# record_revc_ad8228.net
KiCad netlist of a schematic drawn in EAGLE
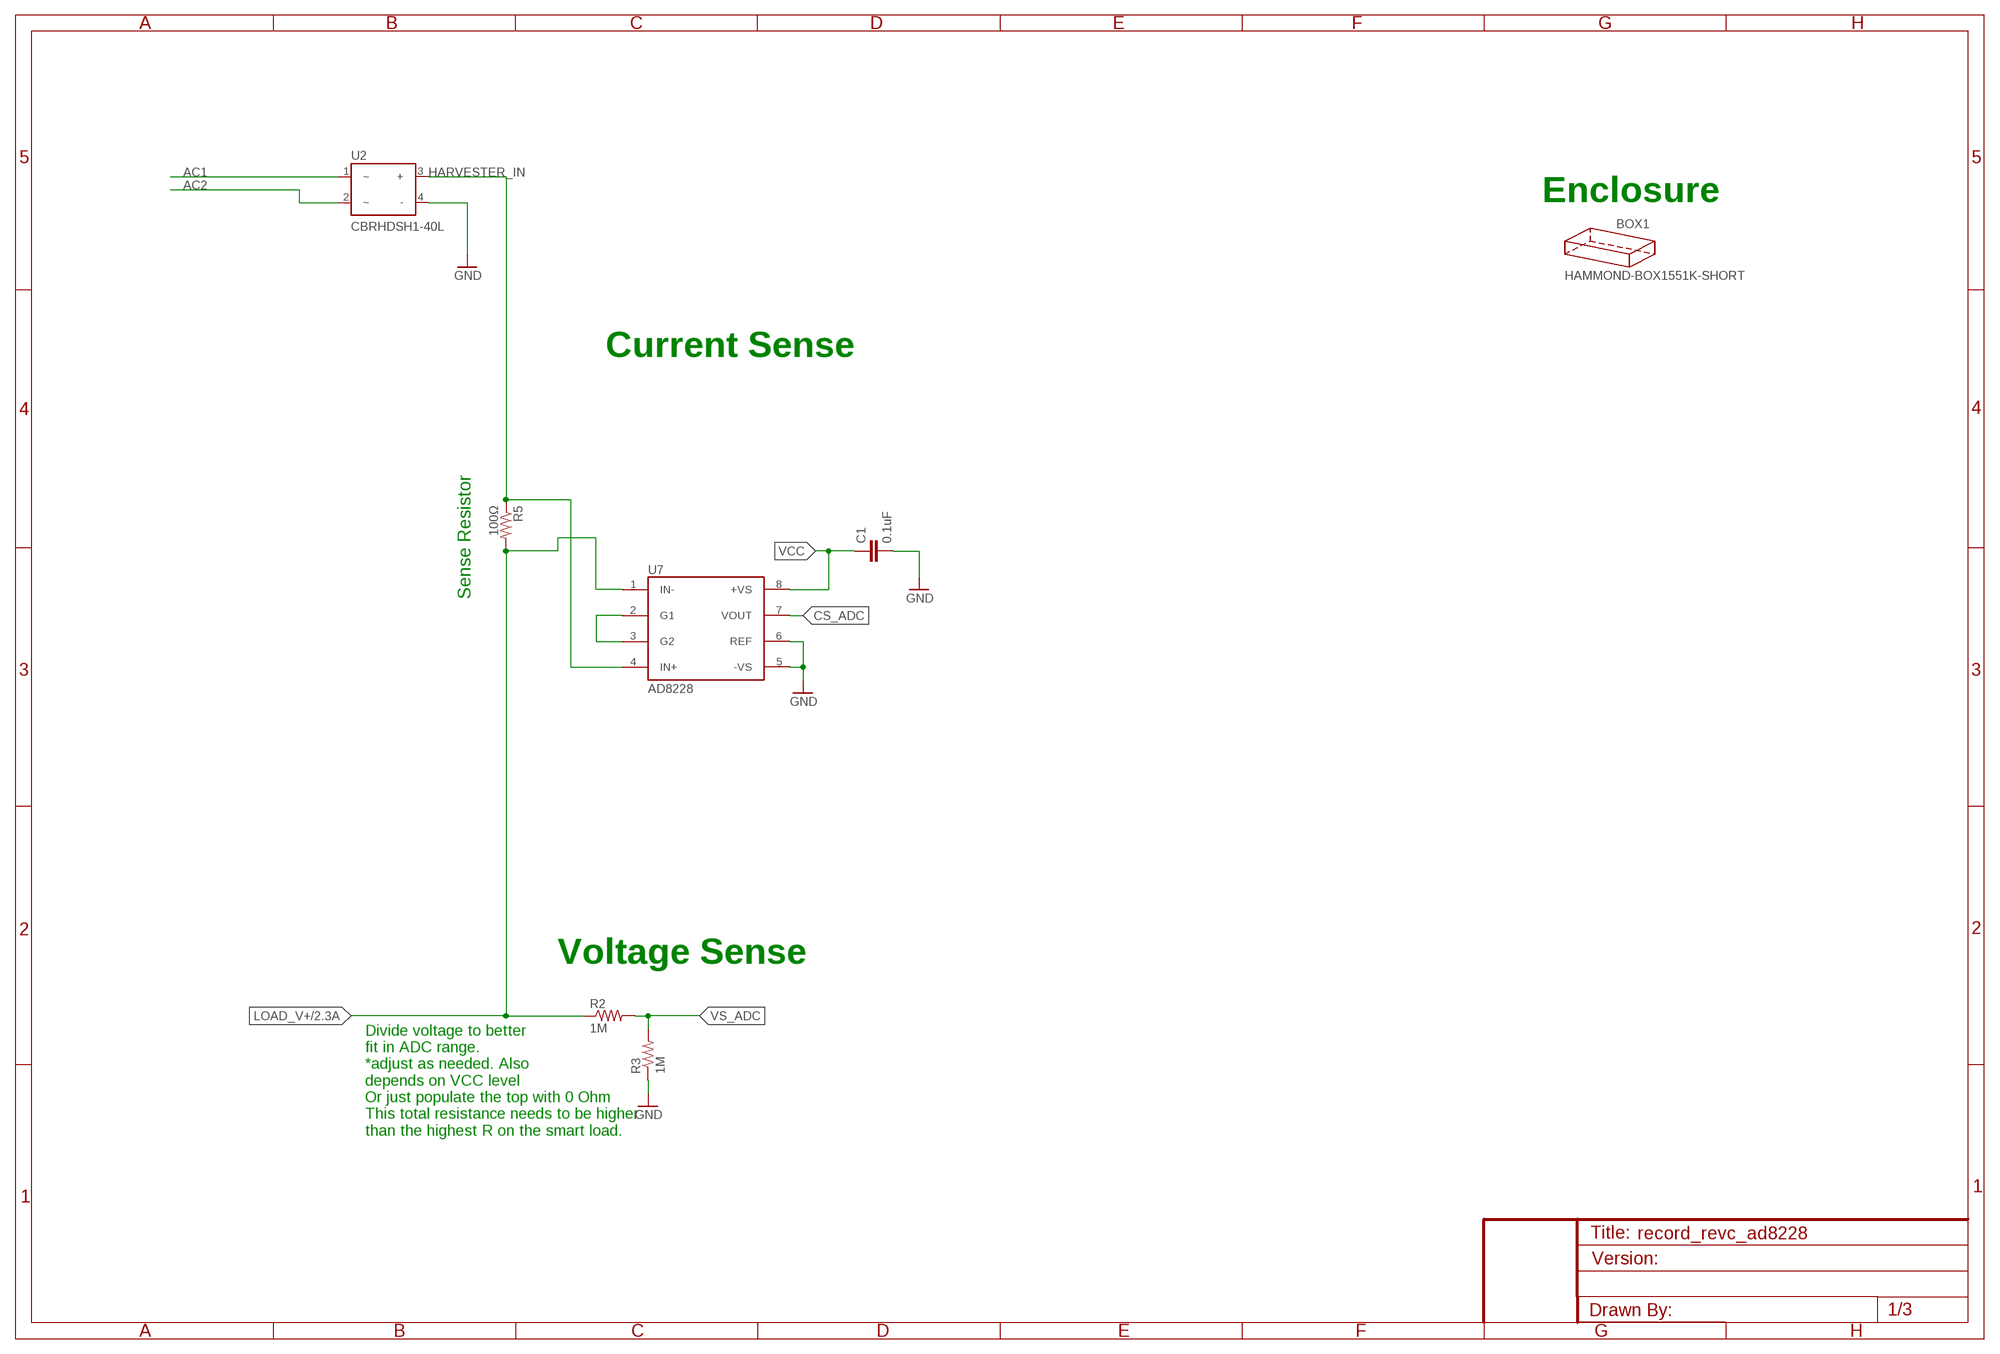
[diagram p0: schematic, sheet 1]
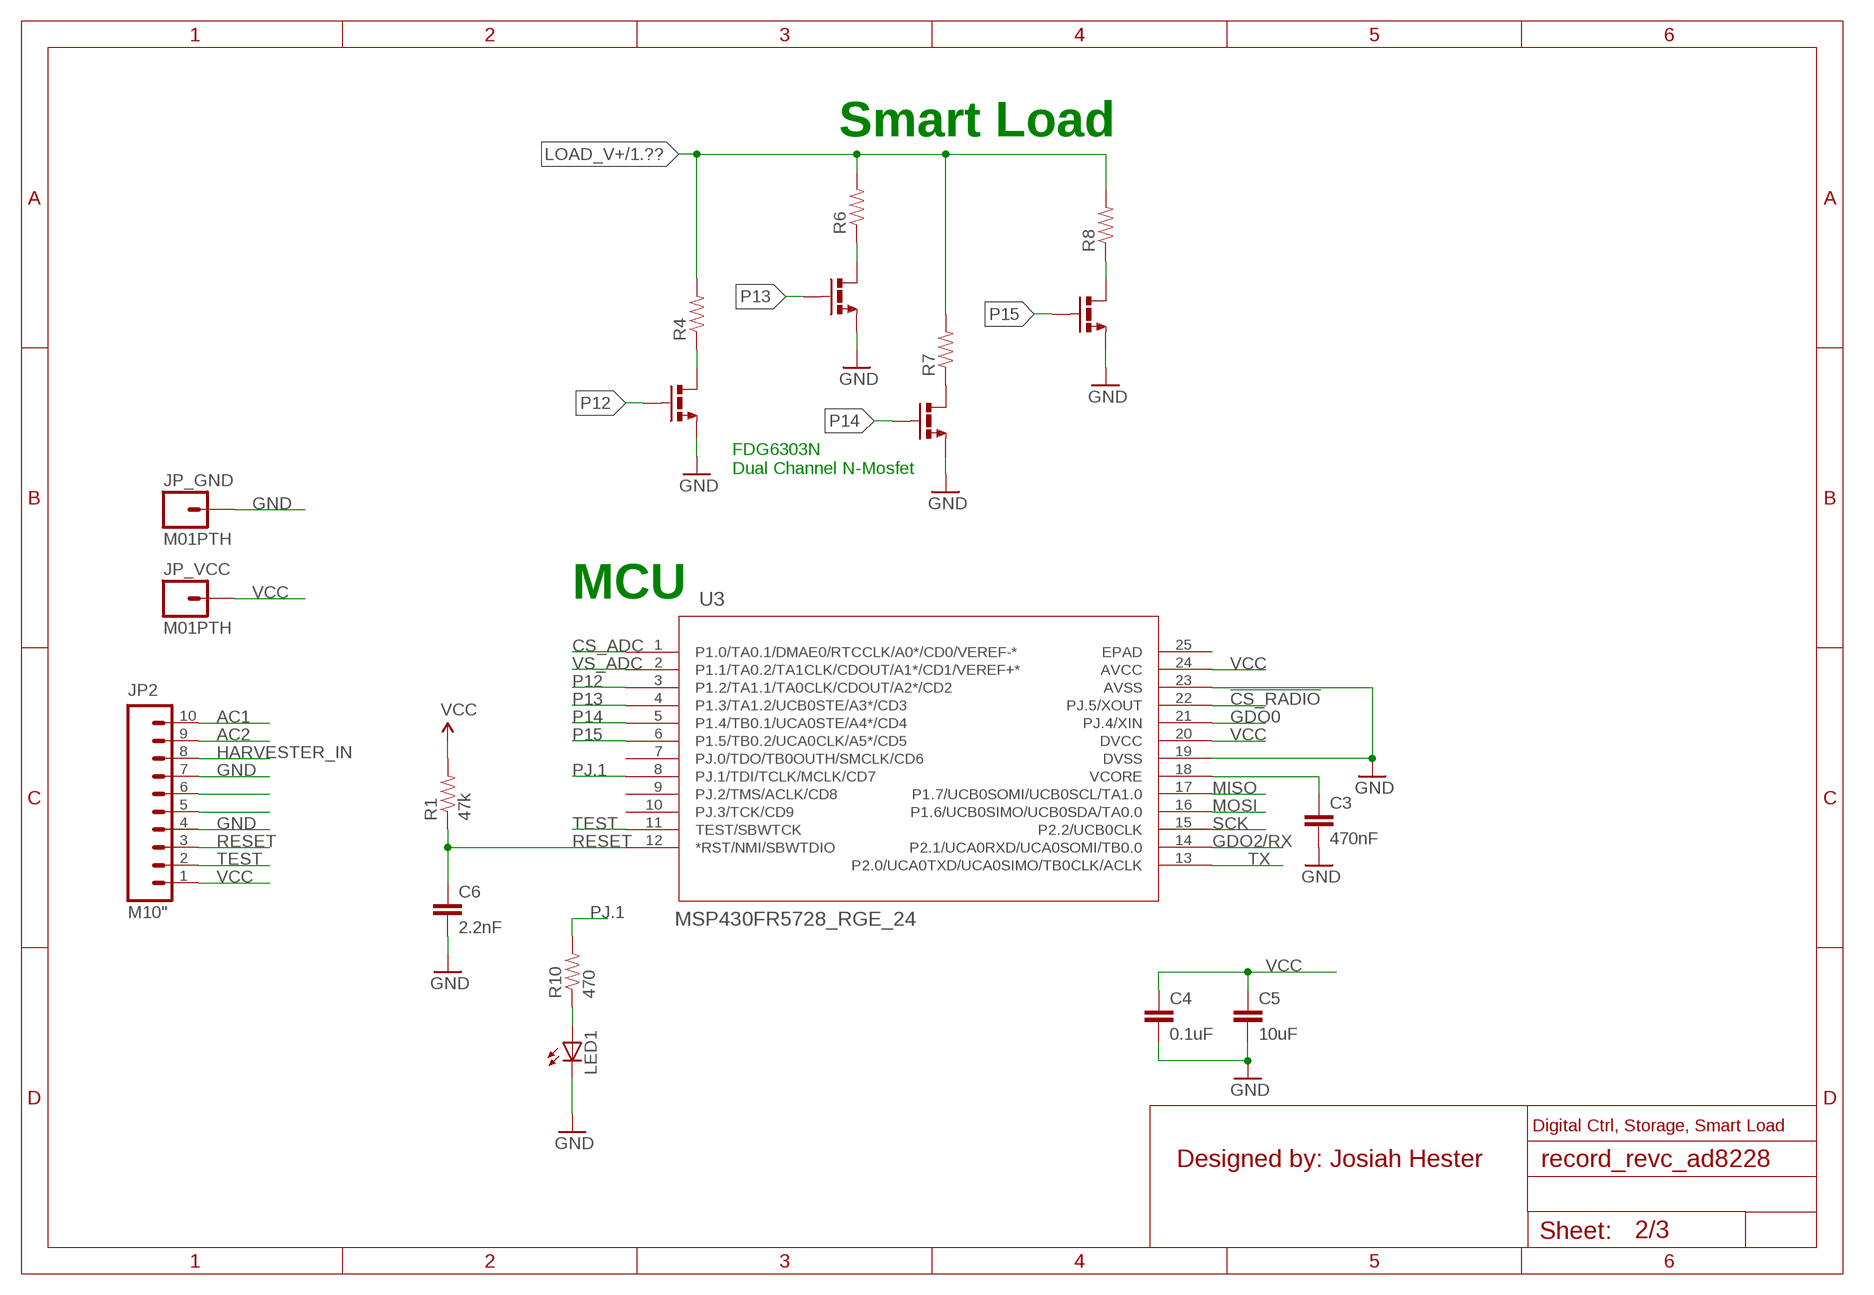
[diagram p1: schematic, sheet 2]
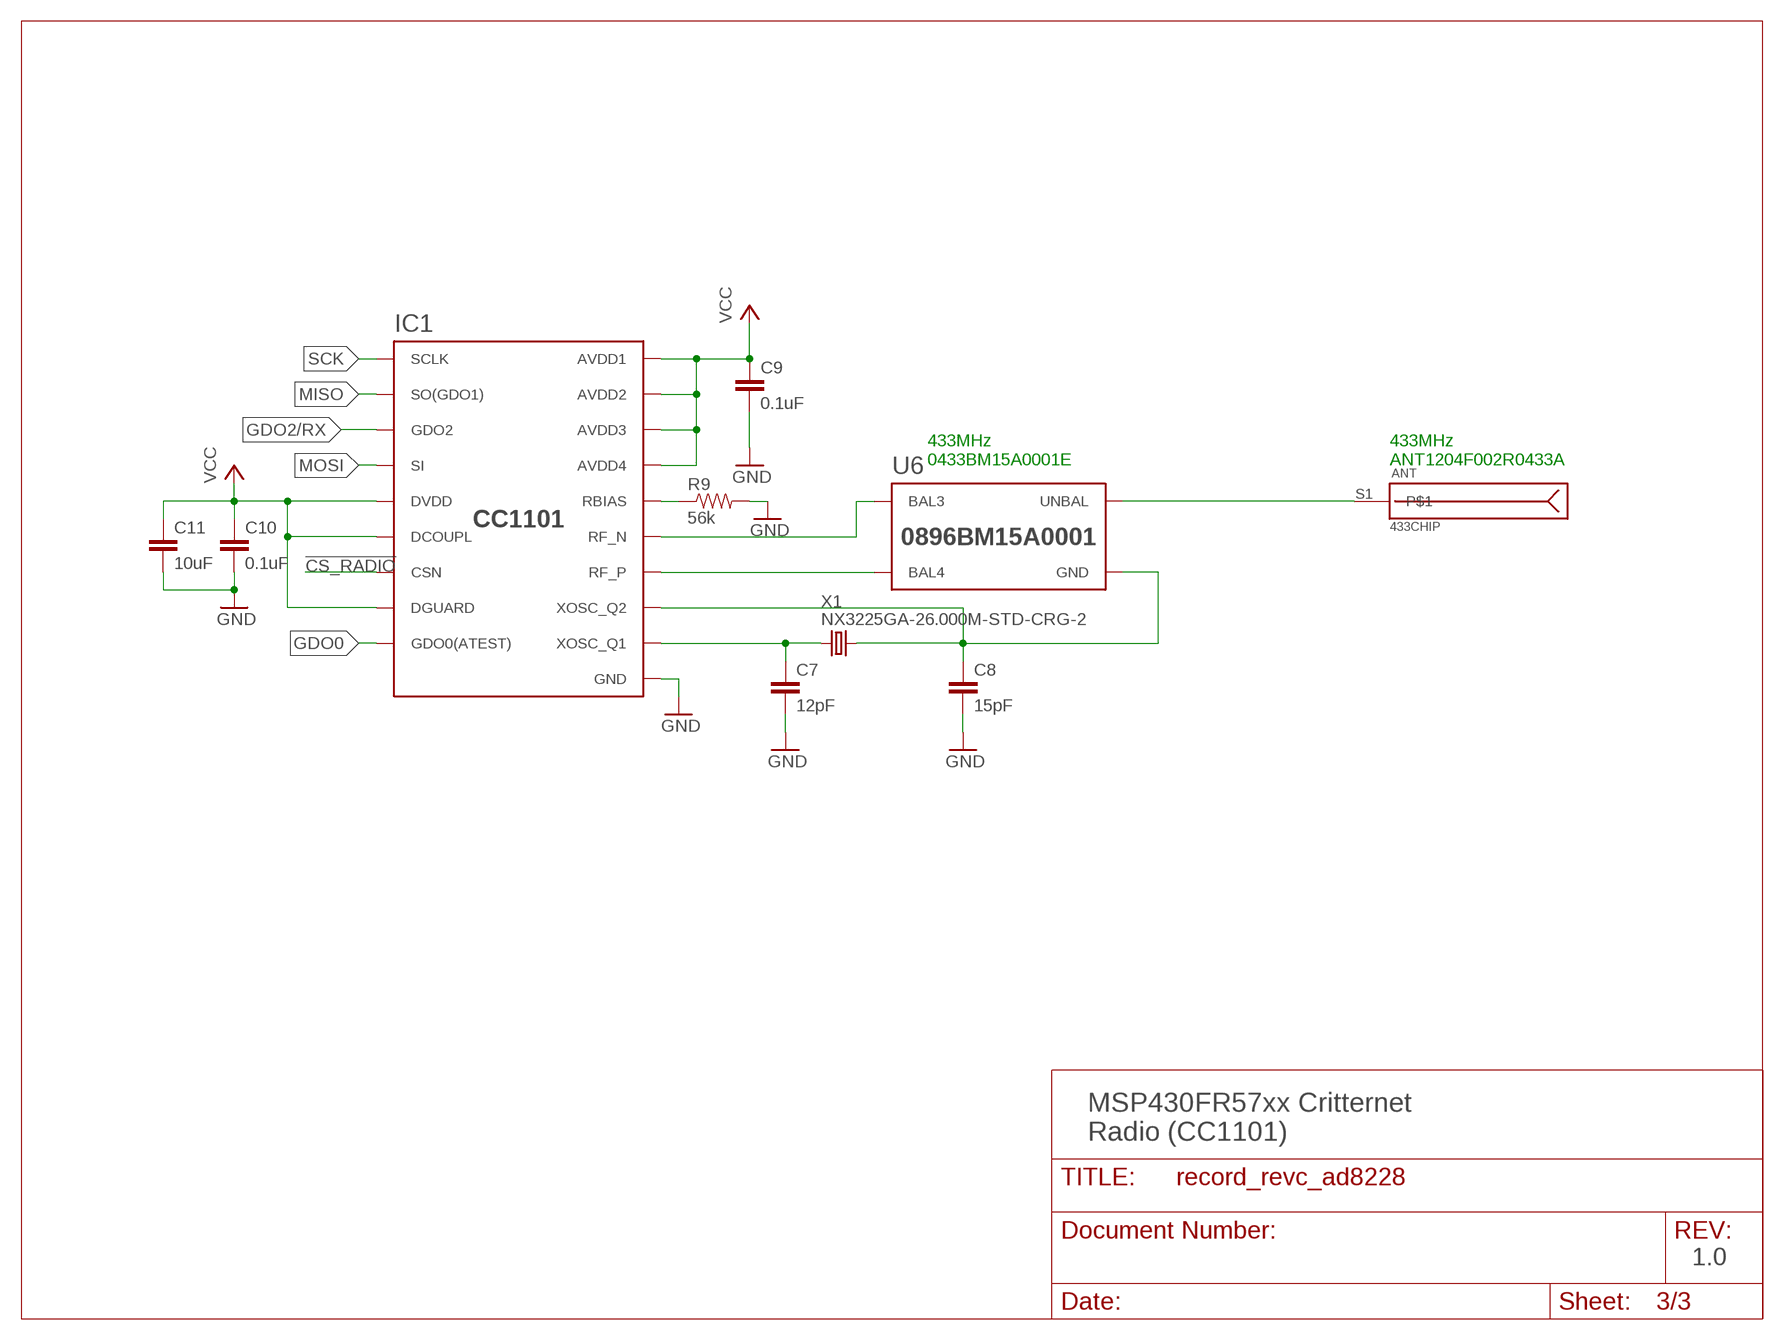
[diagram p2: schematic, sheet 3]

(export (version "E")
  (design (tool "Eeschema 10.0.6"))
  (components
    (comp (ref "BOX1")
      (value "HAMMOND-BOX1551K-SHORT")
      (footprint "eagle-import:1551K-SHORT")
      (libsource (lib "eagle-import") (part "HAMMOND-BOX1551K-SHORT"))
    )
    (comp (ref "C1")
      (value "0.1uF")
      (footprint "eagle-import:C0805")
      (libsource (lib "eagle-import") (part "CAP0805"))
    )
    (comp (ref "R2")
      (value "1M")
      (footprint "eagle-import:0805")
      (libsource (lib "eagle-import") (part "SparkFun-Resistors_RESISTOR0805-RES"))
    )
    (comp (ref "R3")
      (value "1M")
      (footprint "eagle-import:0805")
      (libsource (lib "eagle-import") (part "SparkFun-Resistors_RESISTOR0805-RES"))
    )
    (comp (ref "R5")
      (value "100Ω")
      (footprint "eagle-import:0805")
      (libsource (lib "eagle-import") (part "RESISTOR0805-RES"))
    )
    (comp (ref "U2")
      (value "CBRHDSH1-40L")
      (footprint "eagle-import:HD_DIP4")
      (libsource (lib "eagle-import") (part "CBRHDSH1-40L"))
    )
    (comp (ref "U7")
      (value "AD8228")
      (footprint "eagle-import:MSOP8")
      (libsource (lib "eagle-import") (part "AD8228"))
    )
    (comp (ref "ANT")
      (value "433CHIP")
      (footprint "eagle-import:ANT-433-USP")
      (libsource (lib "eagle-import") (part "433CHIP"))
    )
    (comp (ref "C7")
      (value "12pF")
      (footprint "eagle-import:0603-CAP")
      (libsource (lib "eagle-import") (part "0.1UF-25V(+80/-20%)(0603)"))
    )
    (comp (ref "C8")
      (value "15pF")
      (footprint "eagle-import:0603-CAP")
      (libsource (lib "eagle-import") (part "0.1UF-25V(+80/-20%)(0603)"))
    )
    (comp (ref "C9")
      (value "0.1uF")
      (footprint "eagle-import:0603-CAP")
      (libsource (lib "eagle-import") (part "CAP0603-CAP"))
    )
    (comp (ref "C10")
      (value "0.1uF")
      (footprint "eagle-import:C0805")
      (libsource (lib "eagle-import") (part "CAP0805"))
    )
    (comp (ref "C11")
      (value "10uF")
      (footprint "eagle-import:0805")
      (libsource (lib "eagle-import") (part "1.0UF-25V-+80/-20(0805)"))
    )
    (comp (ref "IC1")
      (value "CC1101")
      (footprint "eagle-import:QLP20")
      (libsource (lib "eagle-import") (part "CC1101"))
    )
    (comp (ref "R9")
      (value "56k")
      (footprint "eagle-import:0603")
      (libsource (lib "eagle-import") (part "0OHM1/10W5%(0603)"))
    )
    (comp (ref "U6")
      (value "0896BM15A0001")
      (footprint "eagle-import:0896BM15A0001")
      (libsource (lib "eagle-import") (part "0896BM15A0001"))
    )
    (comp (ref "X1")
      (value "NX3225GA-26.000M-STD-CRG-2")
      (footprint "eagle-import:XTAL-3.2X2.5")
      (libsource (lib "eagle-import") (part "XTAL-3.2X2.5"))
    )
    (comp (ref "C3")
      (value "470nF")
      (footprint "eagle-import:0805")
      (libsource (lib "eagle-import") (part "1UF-25V-10%(0805)"))
    )
    (comp (ref "C4")
      (value "0.1uF")
      (footprint "eagle-import:0805")
      (libsource (lib "eagle-import") (part "1UF-25V-10%(0805)"))
    )
    (comp (ref "C5")
      (value "10uF")
      (footprint "eagle-import:0805")
      (libsource (lib "eagle-import") (part "1UF-25V-10%(0805)"))
    )
    (comp (ref "C6")
      (value "2.2nF")
      (footprint "eagle-import:0805")
      (libsource (lib "eagle-import") (part "1UF-25V-10%(0805)"))
    )
    (comp (ref "JP2")
      (value "M10\"")
      (footprint "eagle-import:1X10")
      (libsource (lib "eagle-import") (part "M10{dblquote}"))
    )
    (comp (ref "JP_GND")
      (value "M01PTH")
      (footprint "eagle-import:1X01")
      (libsource (lib "eagle-import") (part "M01PTH"))
    )
    (comp (ref "JP_VCC")
      (value "M01PTH")
      (footprint "eagle-import:1X01")
      (libsource (lib "eagle-import") (part "M01PTH"))
    )
    (comp (ref "LED1")
      (value "LED0603")
      (footprint "eagle-import:LED-0603")
      (libsource (lib "eagle-import") (part "LED0603"))
    )
    (comp (ref "R1")
      (value "47k")
      (footprint "eagle-import:0805")
      (libsource (lib "eagle-import") (part "0.22OHM1/4W1%(0805)"))
    )
    (comp (ref "R4")
      (value "0.22OHM1/4W1%(0805)")
      (footprint "eagle-import:0805")
      (libsource (lib "eagle-import") (part "0.22OHM1/4W1%(0805)"))
    )
    (comp (ref "R6")
      (value "0.22OHM1/4W1%(0805)")
      (footprint "eagle-import:0805")
      (libsource (lib "eagle-import") (part "0.22OHM1/4W1%(0805)"))
    )
    (comp (ref "R7")
      (value "0.22OHM1/4W1%(0805)")
      (footprint "eagle-import:0805")
      (libsource (lib "eagle-import") (part "0.22OHM1/4W1%(0805)"))
    )
    (comp (ref "R8")
      (value "0.22OHM1/4W1%(0805)")
      (footprint "eagle-import:0805")
      (libsource (lib "eagle-import") (part "0.22OHM1/4W1%(0805)"))
    )
    (comp (ref "R10")
      (value "470")
      (footprint "eagle-import:0805")
      (libsource (lib "eagle-import") (part "0.22OHM1/4W1%(0805)"))
    )
    (comp (ref "U3")
      (value "MSP430FR5728_RGE_24")
      (footprint "eagle-import:RGE24_2P1X2P1")
      (fields
        (field (name "GENERIC_PART_NUMBER") "MSP430FR5728")
        (field (name "MANUFACTURER") "Texas Instruments")
        (field (name "MANUFACTURER_PART_NUMBER") "msp430fr5728_rge_24")
      )
      (libsource (lib "eagle-import") (part "MSP430FR5728_RGE_24"))
    )
    (comp (ref "U4")
      (value "FDG6303N")
      (footprint "eagle-import:SC70-6")
      (libsource (lib "eagle-import") (part "FDG6303N"))
    )
    (comp (ref "U5")
      (value "FDG6303N")
      (footprint "eagle-import:SC70-6")
      (libsource (lib "eagle-import") (part "FDG6303N"))
    )
  )
  (nets
    (net (code "1") (name "AC1") (class "Default")
      (node (ref "JP2") (pin "10") (pinfunction "10_10") (pintype "passive"))
      (node (ref "U2") (pin "1") (pinfunction "~_1") (pintype "bidirectional"))
    )
    (net (code "2") (name "AC2") (class "Default")
      (node (ref "JP2") (pin "9") (pinfunction "9_9") (pintype "passive"))
      (node (ref "U2") (pin "2") (pinfunction "~_2") (pintype "bidirectional"))
    )
    (net (code "3") (name "CS_ADC") (class "Default")
      (node (ref "U3") (pin "1") (pinfunction "P1.0/TA0.1/DMAE0/RTCCLK/A0*/CD0/VEREF-*_1") (pintype "bidirectional"))
      (node (ref "U7") (pin "7") (pinfunction "VOUT_7") (pintype "bidirectional"))
    )
    (net (code "4") (name "GDO0") (class "Default")
      (node (ref "IC1") (pin "6") (pinfunction "GDO0(ATEST)_6") (pintype "bidirectional"))
      (node (ref "U3") (pin "21") (pinfunction "PJ.4/XIN_21") (pintype "bidirectional"))
    )
    (net (code "5") (name "GDO2{slash}RX") (class "Default")
      (node (ref "IC1") (pin "3") (pinfunction "GDO2_3") (pintype "bidirectional"))
      (node (ref "JP2") (pin "6") (pinfunction "6_6") (pintype "passive"))
      (node (ref "U3") (pin "14") (pinfunction "P2.1/UCA0RXD/UCA0SOMI/TB0.0_14") (pintype "bidirectional"))
    )
    (net (code "6") (name "GND") (class "Default")
      (node (ref "C1") (pin "2") (pinfunction "2_2") (pintype "passive"))
      (node (ref "C10") (pin "2") (pinfunction "2_2") (pintype "passive"))
      (node (ref "C11") (pin "2") (pinfunction "2_2") (pintype "passive"))
      (node (ref "C3") (pin "2") (pinfunction "2_2") (pintype "passive"))
      (node (ref "C4") (pin "2") (pinfunction "2_2") (pintype "passive"))
      (node (ref "C5") (pin "2") (pinfunction "2_2") (pintype "passive"))
      (node (ref "C6") (pin "2") (pinfunction "2_2") (pintype "passive"))
      (node (ref "C7") (pin "2") (pinfunction "2_2") (pintype "passive"))
      (node (ref "C8") (pin "2") (pinfunction "2_2") (pintype "passive"))
      (node (ref "C9") (pin "2") (pinfunction "2_2") (pintype "passive"))
      (node (ref "IC1") (pin "16") (pinfunction "GND_16") (pintype "bidirectional"))
      (node (ref "IC1") (pin "19") (pinfunction "GND_19") (pintype "bidirectional"))
      (node (ref "IC1") (pin "GND") (pinfunction "GND_GND") (pintype "bidirectional"))
      (node (ref "IC1") (pin "GND1") (pinfunction "GND_GND1") (pintype "bidirectional"))
      (node (ref "IC1") (pin "GND2") (pinfunction "GND_GND2") (pintype "bidirectional"))
      (node (ref "IC1") (pin "GND3") (pinfunction "GND_GND3") (pintype "bidirectional"))
      (node (ref "IC1") (pin "GND4") (pinfunction "GND_GND4") (pintype "bidirectional"))
      (node (ref "IC1") (pin "GND5") (pinfunction "GND_GND5") (pintype "bidirectional"))
      (node (ref "JP2") (pin "4") (pinfunction "4_4") (pintype "passive"))
      (node (ref "JP2") (pin "7") (pinfunction "7_7") (pintype "passive"))
      (node (ref "JP_GND") (pin "1") (pinfunction "1_1") (pintype "passive"))
      (node (ref "LED1") (pin "C") (pinfunction "C_C") (pintype "passive"))
      (node (ref "R3") (pin "1") (pinfunction "1_1") (pintype "passive"))
      (node (ref "R9") (pin "2") (pinfunction "2_2") (pintype "passive"))
      (node (ref "U2") (pin "4") (pinfunction "-_4") (pintype "bidirectional"))
      (node (ref "U3") (pin "19") (pinfunction "DVSS_19") (pintype "power_in"))
      (node (ref "U3") (pin "23") (pinfunction "AVSS_23") (pintype "power_in"))
      (node (ref "U4") (pin "1") (pinfunction "S2_1") (pintype "passive"))
      (node (ref "U4") (pin "4") (pinfunction "S1_4") (pintype "passive"))
      (node (ref "U5") (pin "1") (pinfunction "S2_1") (pintype "passive"))
      (node (ref "U5") (pin "4") (pinfunction "S1_4") (pintype "passive"))
      (node (ref "U7") (pin "5") (pinfunction "-VS_5") (pintype "bidirectional"))
      (node (ref "U7") (pin "6") (pinfunction "REF_6") (pintype "bidirectional"))
    )
    (net (code "7") (name "HARVESTER_IN") (class "Default")
      (node (ref "JP2") (pin "8") (pinfunction "8_8") (pintype "passive"))
      (node (ref "R5") (pin "1") (pinfunction "1_1") (pintype "passive"))
      (node (ref "U2") (pin "3") (pinfunction "+_3") (pintype "bidirectional"))
      (node (ref "U7") (pin "4") (pinfunction "IN+_4") (pintype "bidirectional"))
    )
    (net (code "8") (name "LOAD_V+") (class "Default")
      (node (ref "R2") (pin "1") (pinfunction "1_1") (pintype "passive"))
      (node (ref "R4") (pin "2") (pinfunction "2_2") (pintype "passive"))
      (node (ref "R5") (pin "2") (pinfunction "2_2") (pintype "passive"))
      (node (ref "R6") (pin "2") (pinfunction "2_2") (pintype "passive"))
      (node (ref "R7") (pin "2") (pinfunction "2_2") (pintype "passive"))
      (node (ref "R8") (pin "2") (pinfunction "2_2") (pintype "passive"))
      (node (ref "U7") (pin "1") (pinfunction "IN-_1") (pintype "bidirectional"))
    )
    (net (code "9") (name "MISO") (class "Default")
      (node (ref "IC1") (pin "2") (pinfunction "SO(GDO1)_2") (pintype "bidirectional"))
      (node (ref "U3") (pin "17") (pinfunction "P1.7/UCB0SOMI/UCB0SCL/TA1.0_17") (pintype "bidirectional"))
    )
    (net (code "10") (name "MOSI") (class "Default")
      (node (ref "IC1") (pin "20") (pinfunction "SI_20") (pintype "bidirectional"))
      (node (ref "U3") (pin "16") (pinfunction "P1.6/UCB0SIMO/UCB0SDA/TA0.0_16") (pintype "bidirectional"))
    )
    (net (code "11") (name "Net-(ANT-P$1)") (class "Default")
      (node (ref "ANT") (pin "S1") (pinfunction "P$1_S1") (pintype "bidirectional"))
      (node (ref "U6") (pin "1") (pinfunction "UNBAL_1") (pintype "bidirectional"))
    )
    (net (code "12") (name "Net-(IC1-RBIAS)") (class "Default")
      (node (ref "IC1") (pin "17") (pinfunction "RBIAS_17") (pintype "bidirectional"))
      (node (ref "R9") (pin "1") (pinfunction "1_1") (pintype "passive"))
    )
    (net (code "13") (name "Net-(IC1-RF_N)") (class "Default")
      (node (ref "IC1") (pin "13") (pinfunction "RF_N_13") (pintype "bidirectional"))
      (node (ref "U6") (pin "3") (pinfunction "BAL3_3") (pintype "bidirectional"))
    )
    (net (code "14") (name "Net-(IC1-RF_P)") (class "Default")
      (node (ref "IC1") (pin "12") (pinfunction "RF_P_12") (pintype "bidirectional"))
      (node (ref "U6") (pin "4") (pinfunction "BAL4_4") (pintype "bidirectional"))
    )
    (net (code "15") (name "Net-(IC1-XOSC_Q1)") (class "Default")
      (node (ref "C7") (pin "1") (pinfunction "1_1") (pintype "passive"))
      (node (ref "IC1") (pin "8") (pinfunction "XOSC_Q1_8") (pintype "bidirectional"))
      (node (ref "X1") (pin "1") (pinfunction "1_1") (pintype "passive"))
    )
    (net (code "16") (name "Net-(IC1-XOSC_Q2)") (class "Default")
      (node (ref "C8") (pin "1") (pinfunction "1_1") (pintype "passive"))
      (node (ref "IC1") (pin "10") (pinfunction "XOSC_Q2_10") (pintype "bidirectional"))
      (node (ref "U6") (pin "2") (pinfunction "GND_2") (pintype "bidirectional"))
      (node (ref "U6") (pin "5") (pinfunction "GND_5") (pintype "bidirectional"))
      (node (ref "U6") (pin "6") (pinfunction "GND_6") (pintype "bidirectional"))
      (node (ref "X1") (pin "3") (pinfunction "2_3") (pintype "passive"))
    )
    (net (code "17") (name "Net-(LED1-PadA)") (class "Default")
      (node (ref "LED1") (pin "A") (pinfunction "A_A") (pintype "passive"))
      (node (ref "R10") (pin "1") (pinfunction "1_1") (pintype "passive"))
    )
    (net (code "18") (name "Net-(U3-VCORE)") (class "Default")
      (node (ref "C3") (pin "1") (pinfunction "1_1") (pintype "passive"))
      (node (ref "U3") (pin "18") (pinfunction "VCORE_18") (pintype "power_in"))
    )
    (net (code "19") (name "Net-(U4-D1)") (class "Default")
      (node (ref "R4") (pin "1") (pinfunction "1_1") (pintype "passive"))
      (node (ref "U4") (pin "3") (pinfunction "D1_3") (pintype "passive"))
    )
    (net (code "20") (name "Net-(U4-D2)") (class "Default")
      (node (ref "R6") (pin "1") (pinfunction "1_1") (pintype "passive"))
      (node (ref "U4") (pin "6") (pinfunction "D2_6") (pintype "passive"))
    )
    (net (code "21") (name "Net-(U5-D1)") (class "Default")
      (node (ref "R7") (pin "1") (pinfunction "1_1") (pintype "passive"))
      (node (ref "U5") (pin "3") (pinfunction "D1_3") (pintype "passive"))
    )
    (net (code "22") (name "Net-(U5-D2)") (class "Default")
      (node (ref "R8") (pin "1") (pinfunction "1_1") (pintype "passive"))
      (node (ref "U5") (pin "6") (pinfunction "D2_6") (pintype "passive"))
    )
    (net (code "23") (name "Net-(U7-G1)") (class "Default")
      (node (ref "U7") (pin "2") (pinfunction "G1_2") (pintype "bidirectional"))
      (node (ref "U7") (pin "3") (pinfunction "G2_3") (pintype "bidirectional"))
    )
    (net (code "24") (name "P12") (class "Default")
      (node (ref "U3") (pin "3") (pinfunction "P1.2/TA1.1/TA0CLK/CDOUT/A2*/CD2_3") (pintype "bidirectional"))
      (node (ref "U4") (pin "5") (pinfunction "G1_5") (pintype "passive"))
    )
    (net (code "25") (name "P13") (class "Default")
      (node (ref "U3") (pin "4") (pinfunction "P1.3/TA1.2/UCB0STE/A3*/CD3_4") (pintype "bidirectional"))
      (node (ref "U4") (pin "2") (pinfunction "G2_2") (pintype "passive"))
    )
    (net (code "26") (name "P14") (class "Default")
      (node (ref "U3") (pin "5") (pinfunction "P1.4/TB0.1/UCA0STE/A4*/CD4_5") (pintype "bidirectional"))
      (node (ref "U5") (pin "5") (pinfunction "G1_5") (pintype "passive"))
    )
    (net (code "27") (name "P15") (class "Default")
      (node (ref "U3") (pin "6") (pinfunction "P1.5/TB0.2/UCA0CLK/A5*/CD5_6") (pintype "bidirectional"))
      (node (ref "U5") (pin "2") (pinfunction "G2_2") (pintype "passive"))
    )
    (net (code "28") (name "PJ.1") (class "Default")
      (node (ref "R10") (pin "2") (pinfunction "2_2") (pintype "passive"))
      (node (ref "U3") (pin "8") (pinfunction "PJ.1/TDI/TCLK/MCLK/CD7_8") (pintype "bidirectional"))
    )
    (net (code "29") (name "RESET") (class "Default")
      (node (ref "C6") (pin "1") (pinfunction "1_1") (pintype "passive"))
      (node (ref "JP2") (pin "3") (pinfunction "3_3") (pintype "passive"))
      (node (ref "R1") (pin "1") (pinfunction "1_1") (pintype "passive"))
      (node (ref "U3") (pin "12") (pinfunction "*RST/NMI/SBWTDIO_12") (pintype "bidirectional"))
    )
    (net (code "30") (name "SCK") (class "Default")
      (node (ref "IC1") (pin "1") (pinfunction "SCLK_1") (pintype "bidirectional"))
      (node (ref "U3") (pin "15") (pinfunction "P2.2/UCB0CLK_15") (pintype "bidirectional"))
    )
    (net (code "31") (name "TEST") (class "Default")
      (node (ref "JP2") (pin "2") (pinfunction "2_2") (pintype "passive"))
      (node (ref "U3") (pin "11") (pinfunction "TEST/SBWTCK_11") (pintype "bidirectional"))
    )
    (net (code "32") (name "TX") (class "Default")
      (node (ref "JP2") (pin "5") (pinfunction "5_5") (pintype "passive"))
      (node (ref "U3") (pin "13") (pinfunction "P2.0/UCA0TXD/UCA0SIMO/TB0CLK/ACLK_13") (pintype "bidirectional"))
    )
    (net (code "33") (name "VCC") (class "Default")
      (node (ref "C1") (pin "1") (pinfunction "1_1") (pintype "passive"))
      (node (ref "C10") (pin "1") (pinfunction "1_1") (pintype "passive"))
      (node (ref "C11") (pin "1") (pinfunction "1_1") (pintype "passive"))
      (node (ref "C4") (pin "1") (pinfunction "1_1") (pintype "passive"))
      (node (ref "C5") (pin "1") (pinfunction "1_1") (pintype "passive"))
      (node (ref "C9") (pin "1") (pinfunction "1_1") (pintype "passive"))
      (node (ref "IC1") (pin "11") (pinfunction "AVDD2_11") (pintype "bidirectional"))
      (node (ref "IC1") (pin "14") (pinfunction "AVDD3_14") (pintype "bidirectional"))
      (node (ref "IC1") (pin "15") (pinfunction "AVDD4_15") (pintype "bidirectional"))
      (node (ref "IC1") (pin "18") (pinfunction "DGUARD_18") (pintype "bidirectional"))
      (node (ref "IC1") (pin "4") (pinfunction "DVDD_4") (pintype "bidirectional"))
      (node (ref "IC1") (pin "5") (pinfunction "DCOUPL_5") (pintype "bidirectional"))
      (node (ref "IC1") (pin "9") (pinfunction "AVDD1_9") (pintype "bidirectional"))
      (node (ref "JP2") (pin "1") (pinfunction "1_1") (pintype "passive"))
      (node (ref "JP_VCC") (pin "1") (pinfunction "1_1") (pintype "passive"))
      (node (ref "R1") (pin "2") (pinfunction "2_2") (pintype "passive"))
      (node (ref "U3") (pin "20") (pinfunction "DVCC_20") (pintype "power_in"))
      (node (ref "U3") (pin "24") (pinfunction "AVCC_24") (pintype "power_in"))
      (node (ref "U7") (pin "8") (pinfunction "+VS_8") (pintype "bidirectional"))
    )
    (net (code "34") (name "VS_ADC") (class "Default")
      (node (ref "R2") (pin "2") (pinfunction "2_2") (pintype "passive"))
      (node (ref "R3") (pin "2") (pinfunction "2_2") (pintype "passive"))
      (node (ref "U3") (pin "2") (pinfunction "P1.1/TA0.2/TA1CLK/CDOUT/A1*/CD1/VEREF+*_2") (pintype "bidirectional"))
    )
    (net (code "35") (name "unconnected-(U3-EPAD-Pad25)") (class "Default")
      (node (ref "U3") (pin "25") (pinfunction "EPAD_25") (pintype "passive"))
    )
    (net (code "36") (name "unconnected-(U3-PJ.0{slash}TDO{slash}TB0OUTH{slash}SMCLK{slash}CD6-Pad7)") (class "Default")
      (node (ref "U3") (pin "7") (pinfunction "PJ.0/TDO/TB0OUTH/SMCLK/CD6_7") (pintype "bidirectional"))
    )
    (net (code "37") (name "unconnected-(U3-PJ.2{slash}TMS{slash}ACLK{slash}CD8-Pad9)") (class "Default")
      (node (ref "U3") (pin "9") (pinfunction "PJ.2/TMS/ACLK/CD8_9") (pintype "bidirectional"))
    )
    (net (code "38") (name "unconnected-(U3-PJ.3{slash}TCK{slash}CD9-Pad10)") (class "Default")
      (node (ref "U3") (pin "10") (pinfunction "PJ.3/TCK/CD9_10") (pintype "bidirectional"))
    )
    (net (code "39") (name "~{CS_RADIO}") (class "Default")
      (node (ref "IC1") (pin "7") (pinfunction "CSN_7") (pintype "bidirectional"))
      (node (ref "U3") (pin "22") (pinfunction "PJ.5/XOUT_22") (pintype "bidirectional"))
    )
  )
)
